# Prueba1.net
KiCad netlist of a schematic drawn in Altium Designer
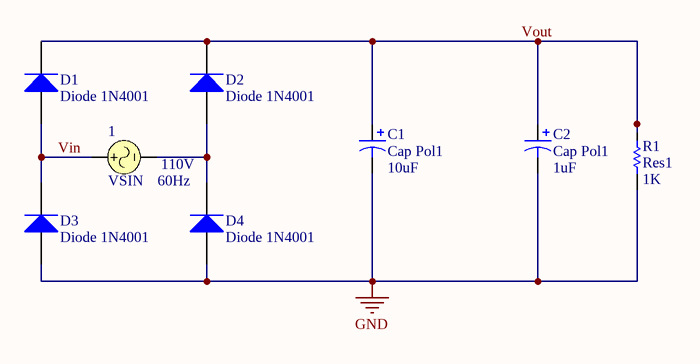
[diagram p0: Prueba1.SchDoc]

(export (version "E")
  (design (tool "Eeschema 10.0.6"))
  (components
    (comp (ref "1")
      (value "VSIN")
      (description "Sinusoidal Voltage Source")
      (fields
        (field (name "AMPLITUDE") "110V")
        (field (name "FREQUENCY") "60Hz")
        (field (name "PUBLISHER") "Altium Limited")
      )
      (libsource (lib "Simulation Sources") (part "VSIN"))
    )
    (comp (ref "C1")
      (value "Cap Pol1")
      (footprint "RB7.6-15")
      (description "Polarized Capacitor (Radial)")
      (fields (field (name "ALTIUM_VALUE") "10uF") (field (name "PUBLISHER") "Altium Limited"))
      (libsource (lib "Miscellaneous Devices") (part "Cap Pol1"))
    )
    (comp (ref "C2")
      (value "Cap Pol1")
      (footprint "RB7.6-15")
      (description "Polarized Capacitor (Radial)")
      (fields (field (name "ALTIUM_VALUE") "1uF") (field (name "PUBLISHER") "Altium Limited"))
      (libsource (lib "Miscellaneous Devices") (part "Cap Pol1"))
    )
    (comp (ref "D1")
      (value "Diode 1N4001")
      (footprint "DO-41")
      (description "1 Amp General Purpose Rectifier")
      (fields (field (name "PUBLISHER") "Altium Limited"))
      (libsource (lib "Miscellaneous Devices") (part "Diode 1N4001"))
    )
    (comp (ref "D2")
      (value "Diode 1N4001")
      (footprint "DO-41")
      (description "1 Amp General Purpose Rectifier")
      (fields (field (name "PUBLISHER") "Altium Limited"))
      (libsource (lib "Miscellaneous Devices") (part "Diode 1N4001"))
    )
    (comp (ref "D3")
      (value "Diode 1N4001")
      (footprint "DO-41")
      (description "1 Amp General Purpose Rectifier")
      (fields (field (name "PUBLISHER") "Altium Limited"))
      (libsource (lib "Miscellaneous Devices") (part "Diode 1N4001"))
    )
    (comp (ref "D4")
      (value "Diode 1N4001")
      (footprint "DO-41")
      (description "1 Amp General Purpose Rectifier")
      (fields (field (name "PUBLISHER") "Altium Limited"))
      (libsource (lib "Miscellaneous Devices") (part "Diode 1N4001"))
    )
    (comp (ref "R1")
      (value "Res1")
      (footprint "AXIAL-0.3")
      (description "Resistor")
      (fields (field (name "ALTIUM_VALUE") "1K") (field (name "PUBLISHER") "Altium Limited"))
      (libsource (lib "Miscellaneous Devices") (part "Res1"))
    )
  )
  (nets
    (net (code "1") (name "/Vin") (class "Default")
      (node (ref "1") (pin "1") (pinfunction "1_1") (pintype "passive"))
      (node (ref "D1") (pin "1") (pinfunction "A_1") (pintype "passive"))
      (node (ref "D3") (pin "2") (pinfunction "K_2") (pintype "passive"))
    )
    (net (code "2") (name "/Vout") (class "Default")
      (node (ref "C1") (pin "1") (pinfunction "1_1") (pintype "passive"))
      (node (ref "C2") (pin "1") (pinfunction "1_1") (pintype "passive"))
      (node (ref "D1") (pin "2") (pinfunction "K_2") (pintype "passive"))
      (node (ref "D2") (pin "2") (pinfunction "K_2") (pintype "passive"))
      (node (ref "R1") (pin "2") (pinfunction "2_2") (pintype "passive"))
    )
    (net (code "3") (name "GND") (class "Default")
      (node (ref "C1") (pin "2") (pinfunction "2_2") (pintype "passive"))
      (node (ref "C2") (pin "2") (pinfunction "2_2") (pintype "passive"))
      (node (ref "D3") (pin "1") (pinfunction "A_1") (pintype "passive"))
      (node (ref "D4") (pin "1") (pinfunction "A_1") (pintype "passive"))
      (node (ref "R1") (pin "1") (pinfunction "1_1") (pintype "passive"))
    )
    (net (code "4") (name "Net-(D2-A)") (class "Default")
      (node (ref "1") (pin "2") (pinfunction "2_2") (pintype "passive"))
      (node (ref "D2") (pin "1") (pinfunction "A_1") (pintype "passive"))
      (node (ref "D4") (pin "2") (pinfunction "K_2") (pintype "passive"))
    )
  )
)
